# PSU.net
KiCad netlist of a schematic drawn in Altium Designer
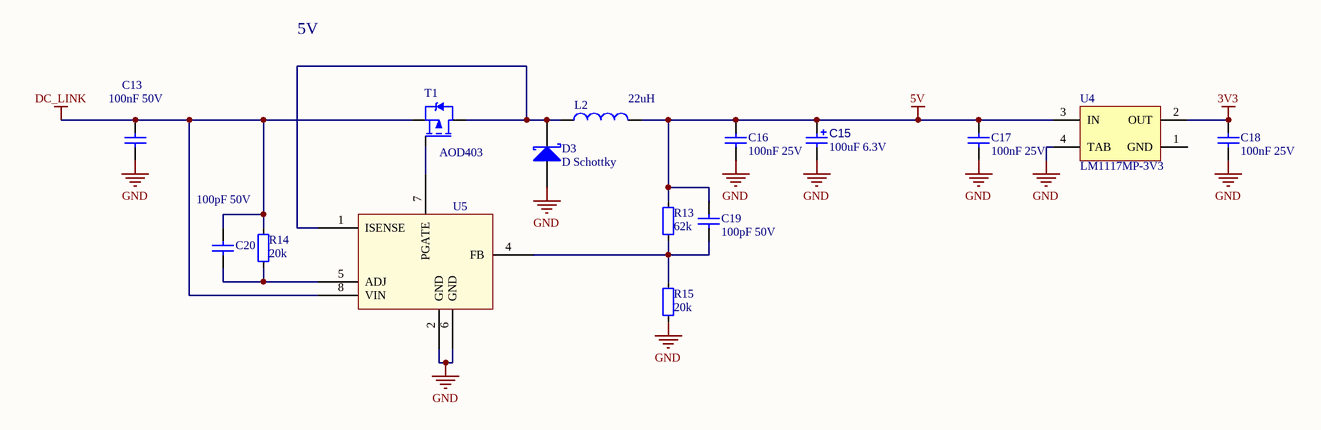
[diagram p0: PSU.SchDoc]

(export (version "E")
  (design (tool "Eeschema 10.0.6"))
  (components
    (comp (ref "C13")
      (value "100nF 50V")
      (footprint "0603_CAP")
      (description "Ceramic capacitor")
      (libsource (lib "Library_Altium_KNR") (part "Cap"))
    )
    (comp (ref "C15")
      (value "100uF 6.3V")
      (footprint "Con_SMD_6.3x5.5")
      (description "Polar capacitor")
      (libsource (lib "Library_Altium_KNR") (part "Cap_Pol"))
    )
    (comp (ref "C16")
      (value "100nF 25V")
      (footprint "0603_CAP")
      (description "Ceramic capacitor")
      (libsource (lib "Library_Altium_KNR") (part "Cap"))
    )
    (comp (ref "C17")
      (value "100nF 25V")
      (footprint "0603_CAP")
      (description "Ceramic capacitor")
      (libsource (lib "Library_Altium_KNR") (part "Cap"))
    )
    (comp (ref "C18")
      (value "100nF 25V")
      (footprint "0603_CAP")
      (description "Ceramic capacitor")
      (libsource (lib "Library_Altium_KNR") (part "Cap"))
    )
    (comp (ref "C19")
      (value "100pF 50V")
      (footprint "0603_CAP")
      (description "Ceramic capacitor")
      (libsource (lib "Library_Altium_KNR") (part "Cap"))
    )
    (comp (ref "C20")
      (value "100pF 50V")
      (footprint "0603_CAP")
      (description "Ceramic capacitor")
      (libsource (lib "Library_Altium_KNR") (part "Cap"))
    )
    (comp (ref "D3")
      (value "D Schottky")
      (footprint "SMB")
      (description "Schottky Diode")
      (fields (field (name "PUBLISHER") "Altium Limited"))
      (libsource (lib "Miscellaneous Devices") (part "D Schottky"))
    )
    (comp (ref "L2")
      (value "22uH")
      (footprint "Inductors:PA4341.223ANLT")
      (libsource (lib "my_lib_ext") (part "Inductor"))
    )
    (comp (ref "R13")
      (value "62k")
      (footprint "0603")
      (description "Resistior")
      (libsource (lib "Library_Altium_KNR") (part "RES"))
    )
    (comp (ref "R14")
      (value "20k")
      (footprint "0603")
      (description "Resistior")
      (libsource (lib "Library_Altium_KNR") (part "RES"))
    )
    (comp (ref "R15")
      (value "20k")
      (footprint "0603")
      (description "Resistior")
      (libsource (lib "Library_Altium_KNR") (part "RES"))
    )
    (comp (ref "T1")
      (value "AOD403")
      (footprint "DPAK TO-252")
      (description "AEC Generic p-mosfet")
      (libsource (lib "Transistors") (part "p-mosfet"))
    )
    (comp (ref "U4")
      (value "LM1117MP-3V3")
      (footprint "SOT223")
      (description "800mA Low-Dropout Linear Regulator")
      (fields
        (field (name "PARTNUMBER") "LM1117MP-3.3")
        (field (name "MANUFACTURER") "National Semiconductor")
        (field (name "PUBLISHER") "Altium Limited")
      )
      (libsource (lib "Library_Altium_KNR") (part "LM1117MP-3V3"))
    )
    (comp (ref "U5")
      (value "LM3485")
      (footprint "VSSOP8")
      (fields
        (field (name "HELPURL") "C:\\Users\\micha\\Documents\\Studia\\Inżynierka\\Elektronika\\Datasheets\\LM3485.pdf")
      )
      (libsource (lib "Robo_leon") (part "LM3485"))
    )
  )
  (nets
    (net (code "1") (name "3V3") (class "Default")
      (node (ref "C18") (pin "2") (pinfunction "2_2") (pintype "passive"))
      (node (ref "U4") (pin "2") (pinfunction "OUT_2") (pintype "power_in"))
    )
    (net (code "2") (name "5V") (class "Default")
      (node (ref "C15") (pin "1") (pinfunction "1_1") (pintype "passive"))
      (node (ref "C16") (pin "2") (pinfunction "2_2") (pintype "passive"))
      (node (ref "C17") (pin "2") (pinfunction "2_2") (pintype "passive"))
      (node (ref "C19") (pin "2") (pinfunction "2_2") (pintype "passive"))
      (node (ref "L2") (pin "2") (pinfunction "0_2") (pintype "passive"))
      (node (ref "R13") (pin "2") (pinfunction "2_2") (pintype "passive"))
      (node (ref "U4") (pin "3") (pinfunction "IN_3") (pintype "power_in"))
    )
    (net (code "3") (name "DC_LINK") (class "Default")
      (node (ref "C13") (pin "2") (pinfunction "2_2") (pintype "passive"))
      (node (ref "C20") (pin "2") (pinfunction "2_2") (pintype "passive"))
      (node (ref "R14") (pin "2") (pinfunction "2_2") (pintype "passive"))
      (node (ref "T1") (pin "3") (pinfunction "S_3") (pintype "passive"))
      (node (ref "U5") (pin "8") (pinfunction "VIN_8") (pintype "passive"))
    )
    (net (code "4") (name "GND") (class "Default")
      (node (ref "C13") (pin "1") (pinfunction "1_1") (pintype "passive"))
      (node (ref "C15") (pin "2") (pinfunction "2_2") (pintype "passive"))
      (node (ref "C16") (pin "1") (pinfunction "1_1") (pintype "passive"))
      (node (ref "C17") (pin "1") (pinfunction "1_1") (pintype "passive"))
      (node (ref "C18") (pin "1") (pinfunction "1_1") (pintype "passive"))
      (node (ref "D3") (pin "1") (pinfunction "A_1") (pintype "passive"))
      (node (ref "R15") (pin "1") (pinfunction "1_1") (pintype "passive"))
      (node (ref "U4") (pin "4") (pinfunction "TAB_4") (pintype "power_in"))
      (node (ref "U5") (pin "2") (pinfunction "GND_2") (pintype "passive"))
      (node (ref "U5") (pin "6") (pinfunction "GND_6") (pintype "passive"))
    )
    (net (code "5") (name "Net-(D3-K)") (class "Default")
      (node (ref "D3") (pin "2") (pinfunction "K_2") (pintype "passive"))
      (node (ref "L2") (pin "1") (pinfunction "1_1") (pintype "passive"))
      (node (ref "T1") (pin "2") (pinfunction "D_2") (pintype "passive"))
      (node (ref "U5") (pin "1") (pinfunction "ISENSE_1") (pintype "passive"))
    )
    (net (code "6") (name "Net-(T1-G)") (class "Default")
      (node (ref "T1") (pin "1") (pinfunction "G_1") (pintype "passive"))
      (node (ref "U5") (pin "7") (pinfunction "PGATE_7") (pintype "passive"))
    )
    (net (code "7") (name "Net-(U5-ADJ)") (class "Default")
      (node (ref "C20") (pin "1") (pinfunction "1_1") (pintype "passive"))
      (node (ref "R14") (pin "1") (pinfunction "1_1") (pintype "passive"))
      (node (ref "U5") (pin "5") (pinfunction "ADJ_5") (pintype "passive"))
    )
    (net (code "8") (name "Net-(U5-FB)") (class "Default")
      (node (ref "C19") (pin "1") (pinfunction "1_1") (pintype "passive"))
      (node (ref "R13") (pin "1") (pinfunction "1_1") (pintype "passive"))
      (node (ref "R15") (pin "2") (pinfunction "2_2") (pintype "passive"))
      (node (ref "U5") (pin "4") (pinfunction "FB_4") (pintype "passive"))
    )
    (net (code "9") (name "unconnected-(U4-GND-Pad1)") (class "Default")
      (node (ref "U4") (pin "1") (pinfunction "GND_1") (pintype "power_in"))
    )
  )
)
